# untitled.net
KiCad netlist of a schematic drawn in EAGLE
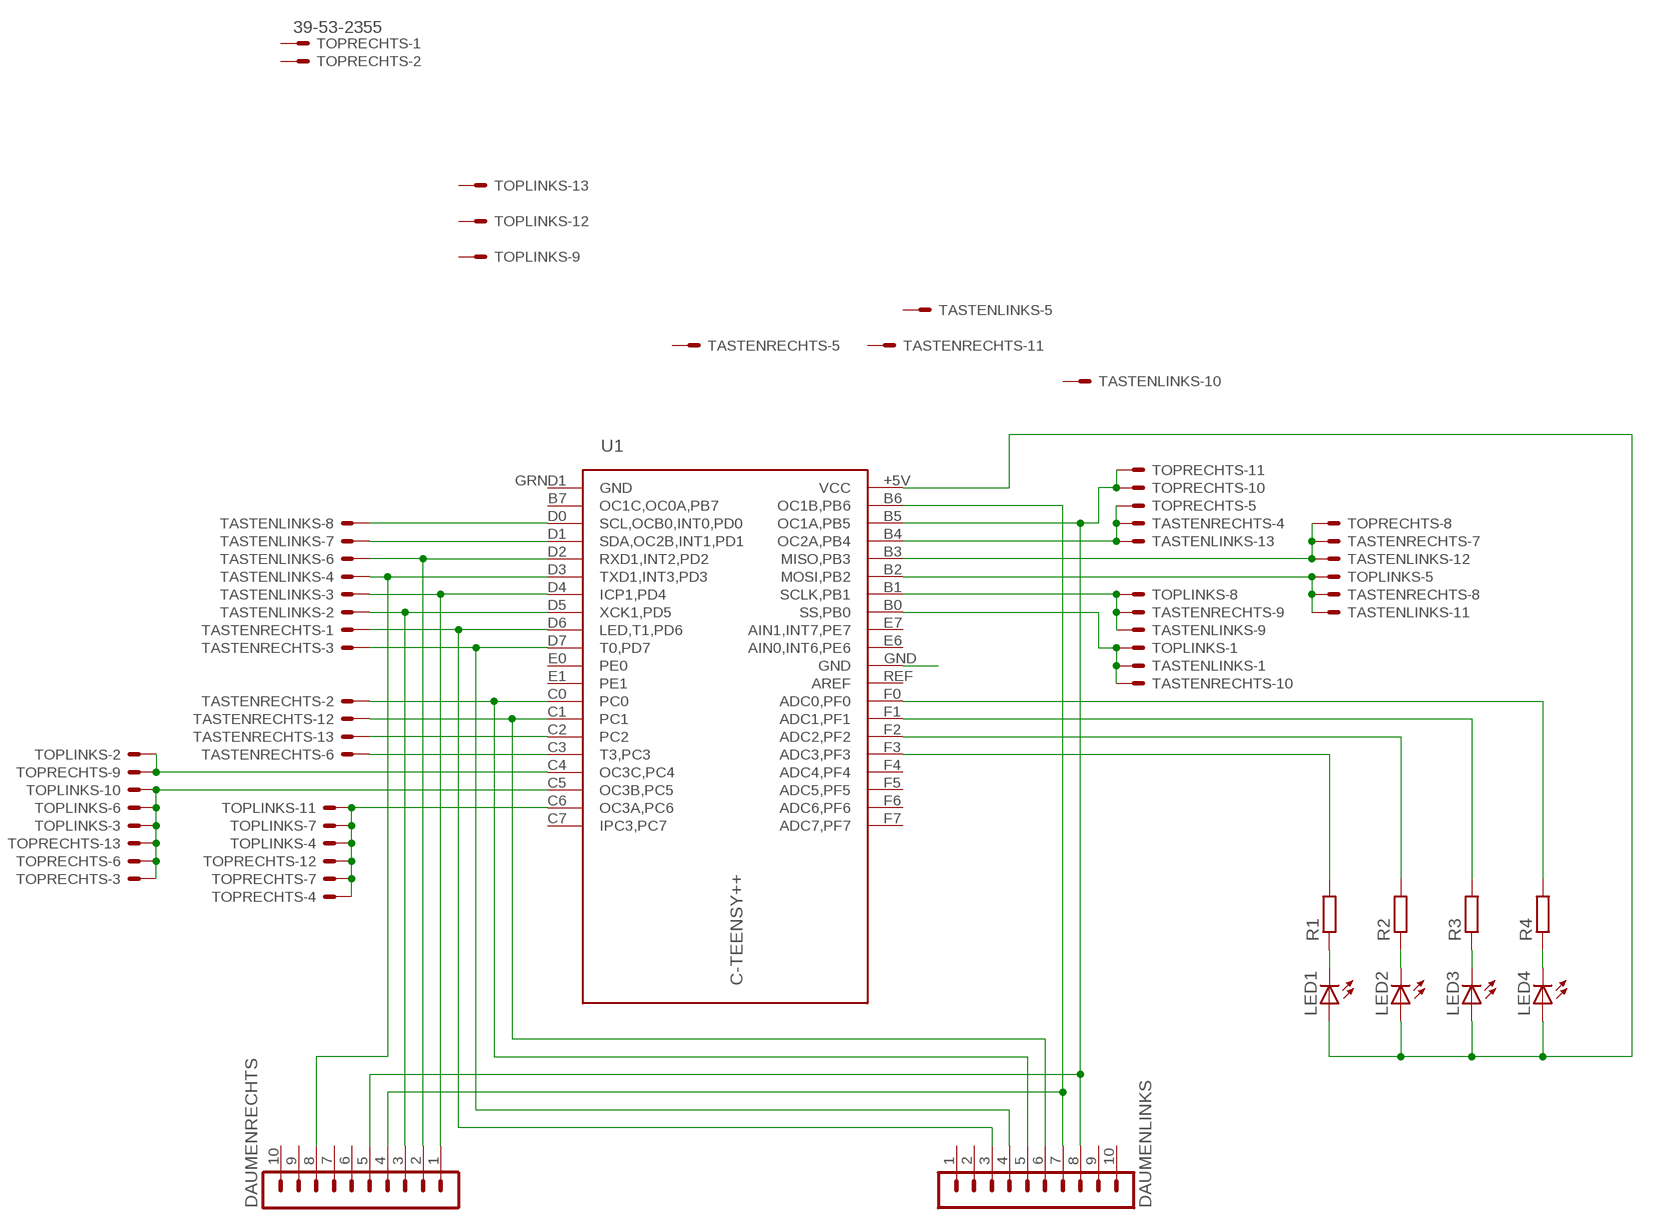
[diagram p0: schematic, sheet 1]

(export (version "E")
  (design (tool "Eeschema 10.0.6"))
  (components
    (comp (ref "DAUMENLINKS")
      (value "MA10-1")
      (footprint "eagle-import:MA10-1")
      (libsource (lib "eagle-import") (part "MA10-1"))
    )
    (comp (ref "DAUMENRECHTS")
      (value "MA10-1")
      (footprint "eagle-import:MA10-1")
      (libsource (lib "eagle-import") (part "MA10-1"))
    )
    (comp (ref "LED1")
      (value "LED3MM")
      (footprint "eagle-import:LED3MM")
      (libsource (lib "eagle-import") (part "LED3MM"))
    )
    (comp (ref "LED2")
      (value "LED3MM")
      (footprint "eagle-import:LED3MM")
      (libsource (lib "eagle-import") (part "LED3MM"))
    )
    (comp (ref "LED3")
      (value "LED3MM")
      (footprint "eagle-import:LED3MM")
      (libsource (lib "eagle-import") (part "LED3MM"))
    )
    (comp (ref "LED4")
      (value "LED3MM")
      (footprint "eagle-import:LED3MM")
      (libsource (lib "eagle-import") (part "LED3MM"))
    )
    (comp (ref "R1")
      (value "R-EU_R1206")
      (footprint "eagle-import:R1206")
      (libsource (lib "eagle-import") (part "R-EU_R1206"))
    )
    (comp (ref "R2")
      (value "R-EU_R1206")
      (footprint "eagle-import:R1206")
      (libsource (lib "eagle-import") (part "R-EU_R1206"))
    )
    (comp (ref "R3")
      (value "R-EU_R1206")
      (footprint "eagle-import:R1206")
      (libsource (lib "eagle-import") (part "R-EU_R1206"))
    )
    (comp (ref "R4")
      (value "R-EU_R1206")
      (footprint "eagle-import:R1206")
      (libsource (lib "eagle-import") (part "R-EU_R1206"))
    )
    (comp (ref "TASTENLINKS")
      (value "39-53-2355")
      (footprint "eagle-import:39-53-2135")
      (libsource (lib "eagle-import") (part "39-53-2355"))
    )
    (comp (ref "TASTENRECHTS")
      (value "39-53-2355")
      (footprint "eagle-import:39-53-2135")
      (libsource (lib "eagle-import") (part "39-53-2355"))
    )
    (comp (ref "TOPLINKS")
      (value "39-53-2355")
      (footprint "eagle-import:39-53-2135")
      (libsource (lib "eagle-import") (part "39-53-2355"))
    )
    (comp (ref "TOPRECHTS")
      (value "39-53-2355")
      (footprint "eagle-import:39-53-2135")
      (libsource (lib "eagle-import") (part "39-53-2355"))
    )
    (comp (ref "U1")
      (value "C-TEENSY++")
      (footprint "eagle-import:TEENSY++")
      (libsource (lib "eagle-import") (part "C-TEENSY++"))
    )
  )
  (nets
    (net (code "1") (name "/GND") (class "Default")
      (node (ref "U1") (pin "GRND1") (pinfunction "GND_GRND1") (pintype "power_in"))
    )
    (net (code "2") (name "Net-(LED1-C)") (class "Default")
      (node (ref "LED1") (pin "K") (pinfunction "C_K") (pintype "passive"))
      (node (ref "R1") (pin "1") (pinfunction "1_1") (pintype "passive"))
    )
    (net (code "3") (name "Net-(LED2-C)") (class "Default")
      (node (ref "LED2") (pin "K") (pinfunction "C_K") (pintype "passive"))
      (node (ref "R2") (pin "1") (pinfunction "1_1") (pintype "passive"))
    )
    (net (code "4") (name "Net-(LED3-C)") (class "Default")
      (node (ref "LED3") (pin "K") (pinfunction "C_K") (pintype "passive"))
      (node (ref "R3") (pin "1") (pinfunction "1_1") (pintype "passive"))
    )
    (net (code "5") (name "Net-(LED4-C)") (class "Default")
      (node (ref "LED4") (pin "K") (pinfunction "C_K") (pintype "passive"))
      (node (ref "R4") (pin "1") (pinfunction "1_1") (pintype "passive"))
    )
    (net (code "6") (name "Net-(TASTENLINKSA-S)") (class "Default")
      (node (ref "TASTENLINKS") (pin "P$1") (pinfunction "S_P$1") (pintype "passive"))
      (node (ref "TASTENRECHTS") (pin "P$10") (pinfunction "S_P$10") (pintype "passive"))
      (node (ref "TOPLINKS") (pin "P$1") (pinfunction "S_P$1") (pintype "passive"))
      (node (ref "U1") (pin "B0") (pinfunction "SS,PB0_B0") (pintype "bidirectional"))
    )
    (net (code "7") (name "Net-(TASTENLINKSC-S)") (class "Default")
      (node (ref "TASTENLINKS") (pin "P$11") (pinfunction "S_P$11") (pintype "passive"))
      (node (ref "TASTENRECHTS") (pin "P$8") (pinfunction "S_P$8") (pintype "passive"))
      (node (ref "TOPLINKS") (pin "P$5") (pinfunction "S_P$5") (pintype "passive"))
      (node (ref "U1") (pin "B2") (pinfunction "MOSI,PB2_B2") (pintype "bidirectional"))
    )
    (net (code "8") (name "Net-(TASTENLINKSD-S)") (class "Default")
      (node (ref "TASTENLINKS") (pin "P$12") (pinfunction "S_P$12") (pintype "passive"))
      (node (ref "TASTENRECHTS") (pin "P$7") (pinfunction "S_P$7") (pintype "passive"))
      (node (ref "TOPRECHTS") (pin "P$8") (pinfunction "S_P$8") (pintype "passive"))
      (node (ref "U1") (pin "B3") (pinfunction "MISO,PB3_B3") (pintype "bidirectional"))
    )
    (net (code "9") (name "Net-(TASTENLINKSE-S)") (class "Default")
      (node (ref "TASTENLINKS") (pin "P$13") (pinfunction "S_P$13") (pintype "passive"))
      (node (ref "TASTENRECHTS") (pin "P$4") (pinfunction "S_P$4") (pintype "passive"))
      (node (ref "TOPRECHTS") (pin "P$5") (pinfunction "S_P$5") (pintype "passive"))
      (node (ref "U1") (pin "B4") (pinfunction "OC2A,PB4_B4") (pintype "bidirectional"))
    )
    (net (code "10") (name "Net-(TASTENLINKSF-S)") (class "Default")
      (node (ref "DAUMENRECHTS") (pin "3") (pinfunction "3_3") (pintype "passive"))
      (node (ref "TASTENLINKS") (pin "P$2") (pinfunction "S_P$2") (pintype "passive"))
      (node (ref "U1") (pin "D5") (pinfunction "XCK1,PD5_D5") (pintype "bidirectional"))
    )
    (net (code "11") (name "Net-(TASTENLINKSG-S)") (class "Default")
      (node (ref "DAUMENRECHTS") (pin "1") (pinfunction "1_1") (pintype "passive"))
      (node (ref "TASTENLINKS") (pin "P$3") (pinfunction "S_P$3") (pintype "passive"))
      (node (ref "U1") (pin "D4") (pinfunction "ICP1,PD4_D4") (pintype "bidirectional"))
    )
    (net (code "12") (name "Net-(TASTENLINKSH-S)") (class "Default")
      (node (ref "DAUMENRECHTS") (pin "8") (pinfunction "8_8") (pintype "passive"))
      (node (ref "TASTENLINKS") (pin "P$4") (pinfunction "S_P$4") (pintype "passive"))
      (node (ref "U1") (pin "D3") (pinfunction "TXD1,INT3,PD3_D3") (pintype "bidirectional"))
    )
    (net (code "13") (name "Net-(TASTENLINKSJ-S)") (class "Default")
      (node (ref "DAUMENRECHTS") (pin "2") (pinfunction "2_2") (pintype "passive"))
      (node (ref "TASTENLINKS") (pin "P$6") (pinfunction "S_P$6") (pintype "passive"))
      (node (ref "U1") (pin "D2") (pinfunction "RXD1,INT2,PD2_D2") (pintype "bidirectional"))
    )
    (net (code "14") (name "Net-(TASTENLINKSK-S)") (class "Default")
      (node (ref "TASTENLINKS") (pin "P$7") (pinfunction "S_P$7") (pintype "passive"))
      (node (ref "U1") (pin "D1") (pinfunction "SDA,OC2B,INT1,PD1_D1") (pintype "bidirectional"))
    )
    (net (code "15") (name "Net-(TASTENLINKSL-S)") (class "Default")
      (node (ref "TASTENLINKS") (pin "P$8") (pinfunction "S_P$8") (pintype "passive"))
      (node (ref "U1") (pin "D0") (pinfunction "SCL,OCB0,INT0,PD0_D0") (pintype "bidirectional"))
    )
    (net (code "16") (name "Net-(TASTENLINKSM-S)") (class "Default")
      (node (ref "TASTENLINKS") (pin "P$9") (pinfunction "S_P$9") (pintype "passive"))
      (node (ref "TASTENRECHTS") (pin "P$9") (pinfunction "S_P$9") (pintype "passive"))
      (node (ref "TOPLINKS") (pin "P$8") (pinfunction "S_P$8") (pintype "passive"))
      (node (ref "U1") (pin "B1") (pinfunction "SCLK,PB1_B1") (pintype "bidirectional"))
    )
    (net (code "17") (name "Net-(TASTENRECHTSA-S)") (class "Default")
      (node (ref "DAUMENLINKS") (pin "3") (pinfunction "3_3") (pintype "passive"))
      (node (ref "TASTENRECHTS") (pin "P$1") (pinfunction "S_P$1") (pintype "passive"))
      (node (ref "U1") (pin "D6") (pinfunction "LED,T1,PD6_D6") (pintype "bidirectional"))
    )
    (net (code "18") (name "Net-(TASTENRECHTSD-S)") (class "Default")
      (node (ref "DAUMENLINKS") (pin "6") (pinfunction "6_6") (pintype "passive"))
      (node (ref "TASTENRECHTS") (pin "P$12") (pinfunction "S_P$12") (pintype "passive"))
      (node (ref "U1") (pin "C1") (pinfunction "PC1_C1") (pintype "bidirectional"))
    )
    (net (code "19") (name "Net-(TASTENRECHTSE-S)") (class "Default")
      (node (ref "TASTENRECHTS") (pin "P$13") (pinfunction "S_P$13") (pintype "passive"))
      (node (ref "U1") (pin "C2") (pinfunction "PC2_C2") (pintype "bidirectional"))
    )
    (net (code "20") (name "Net-(TASTENRECHTSF-S)") (class "Default")
      (node (ref "DAUMENLINKS") (pin "5") (pinfunction "5_5") (pintype "passive"))
      (node (ref "TASTENRECHTS") (pin "P$2") (pinfunction "S_P$2") (pintype "passive"))
      (node (ref "U1") (pin "C0") (pinfunction "PC0_C0") (pintype "bidirectional"))
    )
    (net (code "21") (name "Net-(TASTENRECHTSG-S)") (class "Default")
      (node (ref "DAUMENLINKS") (pin "4") (pinfunction "4_4") (pintype "passive"))
      (node (ref "TASTENRECHTS") (pin "P$3") (pinfunction "S_P$3") (pintype "passive"))
      (node (ref "U1") (pin "D7") (pinfunction "T0,PD7_D7") (pintype "bidirectional"))
    )
    (net (code "22") (name "Net-(TASTENRECHTSJ-S)") (class "Default")
      (node (ref "TASTENRECHTS") (pin "P$6") (pinfunction "S_P$6") (pintype "passive"))
      (node (ref "U1") (pin "C3") (pinfunction "T3,PC3_C3") (pintype "bidirectional"))
    )
    (net (code "23") (name "Net-(TOPLINKSB-S)") (class "Default")
      (node (ref "TOPLINKS") (pin "P$10") (pinfunction "S_P$10") (pintype "passive"))
      (node (ref "TOPLINKS") (pin "P$3") (pinfunction "S_P$3") (pintype "passive"))
      (node (ref "TOPLINKS") (pin "P$6") (pinfunction "S_P$6") (pintype "passive"))
      (node (ref "TOPRECHTS") (pin "P$13") (pinfunction "S_P$13") (pintype "passive"))
      (node (ref "TOPRECHTS") (pin "P$3") (pinfunction "S_P$3") (pintype "passive"))
      (node (ref "TOPRECHTS") (pin "P$6") (pinfunction "S_P$6") (pintype "passive"))
      (node (ref "U1") (pin "C5") (pinfunction "OC3B,PC5_C5") (pintype "bidirectional"))
    )
    (net (code "24") (name "Net-(TOPLINKSC-S)") (class "Default")
      (node (ref "TOPLINKS") (pin "P$11") (pinfunction "S_P$11") (pintype "passive"))
      (node (ref "TOPLINKS") (pin "P$4") (pinfunction "S_P$4") (pintype "passive"))
      (node (ref "TOPLINKS") (pin "P$7") (pinfunction "S_P$7") (pintype "passive"))
      (node (ref "TOPRECHTS") (pin "P$12") (pinfunction "S_P$12") (pintype "passive"))
      (node (ref "TOPRECHTS") (pin "P$4") (pinfunction "S_P$4") (pintype "passive"))
      (node (ref "TOPRECHTS") (pin "P$7") (pinfunction "S_P$7") (pintype "passive"))
      (node (ref "U1") (pin "C6") (pinfunction "OC3A,PC6_C6") (pintype "bidirectional"))
    )
    (net (code "25") (name "Net-(TOPLINKSF-S)") (class "Default")
      (node (ref "TOPLINKS") (pin "P$2") (pinfunction "S_P$2") (pintype "passive"))
      (node (ref "TOPRECHTS") (pin "P$9") (pinfunction "S_P$9") (pintype "passive"))
      (node (ref "U1") (pin "C4") (pinfunction "OC3C,PC4_C4") (pintype "bidirectional"))
    )
    (net (code "26") (name "Net-(TOPRECHTSB-S)") (class "Default")
      (node (ref "DAUMENLINKS") (pin "8") (pinfunction "8_8") (pintype "passive"))
      (node (ref "DAUMENRECHTS") (pin "5") (pinfunction "5_5") (pintype "passive"))
      (node (ref "TOPRECHTS") (pin "P$10") (pinfunction "S_P$10") (pintype "passive"))
      (node (ref "TOPRECHTS") (pin "P$11") (pinfunction "S_P$11") (pintype "passive"))
      (node (ref "U1") (pin "B5") (pinfunction "OC1A,PB5_B5") (pintype "bidirectional"))
    )
    (net (code "27") (name "Net-(U1-ADC0,PF0)") (class "Default")
      (node (ref "R4") (pin "2") (pinfunction "2_2") (pintype "passive"))
      (node (ref "U1") (pin "F0") (pinfunction "ADC0,PF0_F0") (pintype "bidirectional"))
    )
    (net (code "28") (name "Net-(U1-ADC1,PF1)") (class "Default")
      (node (ref "R3") (pin "2") (pinfunction "2_2") (pintype "passive"))
      (node (ref "U1") (pin "F1") (pinfunction "ADC1,PF1_F1") (pintype "bidirectional"))
    )
    (net (code "29") (name "Net-(U1-ADC2,PF2)") (class "Default")
      (node (ref "R2") (pin "2") (pinfunction "2_2") (pintype "passive"))
      (node (ref "U1") (pin "F2") (pinfunction "ADC2,PF2_F2") (pintype "bidirectional"))
    )
    (net (code "30") (name "Net-(U1-ADC3,PF3)") (class "Default")
      (node (ref "R1") (pin "2") (pinfunction "2_2") (pintype "passive"))
      (node (ref "U1") (pin "F3") (pinfunction "ADC3,PF3_F3") (pintype "bidirectional"))
    )
    (net (code "31") (name "Net-(U1-OC1B,PB6)") (class "Default")
      (node (ref "DAUMENLINKS") (pin "7") (pinfunction "7_7") (pintype "passive"))
      (node (ref "DAUMENRECHTS") (pin "4") (pinfunction "4_4") (pintype "passive"))
      (node (ref "U1") (pin "B6") (pinfunction "OC1B,PB6_B6") (pintype "bidirectional"))
    )
    (net (code "32") (name "Net-(U1-VCC)") (class "Default")
      (node (ref "LED1") (pin "A") (pinfunction "A_A") (pintype "passive"))
      (node (ref "LED2") (pin "A") (pinfunction "A_A") (pintype "passive"))
      (node (ref "LED3") (pin "A") (pinfunction "A_A") (pintype "passive"))
      (node (ref "LED4") (pin "A") (pinfunction "A_A") (pintype "passive"))
      (node (ref "U1") (pin "+5V") (pinfunction "VCC_+5V") (pintype "power_in"))
    )
    (net (code "33") (name "unconnected-(DAUMENLINKS-Pad1)") (class "Default")
      (node (ref "DAUMENLINKS") (pin "1") (pinfunction "1_1") (pintype "passive"))
    )
    (net (code "34") (name "unconnected-(DAUMENLINKS-Pad2)") (class "Default")
      (node (ref "DAUMENLINKS") (pin "2") (pinfunction "2_2") (pintype "passive"))
    )
    (net (code "35") (name "unconnected-(DAUMENLINKS-Pad9)") (class "Default")
      (node (ref "DAUMENLINKS") (pin "9") (pinfunction "9_9") (pintype "passive"))
    )
    (net (code "36") (name "unconnected-(DAUMENLINKS-Pad10)") (class "Default")
      (node (ref "DAUMENLINKS") (pin "10") (pinfunction "10_10") (pintype "passive"))
    )
    (net (code "37") (name "unconnected-(DAUMENRECHTS-Pad6)") (class "Default")
      (node (ref "DAUMENRECHTS") (pin "6") (pinfunction "6_6") (pintype "passive"))
    )
    (net (code "38") (name "unconnected-(DAUMENRECHTS-Pad7)") (class "Default")
      (node (ref "DAUMENRECHTS") (pin "7") (pinfunction "7_7") (pintype "passive"))
    )
    (net (code "39") (name "unconnected-(DAUMENRECHTS-Pad9)") (class "Default")
      (node (ref "DAUMENRECHTS") (pin "9") (pinfunction "9_9") (pintype "passive"))
    )
    (net (code "40") (name "unconnected-(DAUMENRECHTS-Pad10)") (class "Default")
      (node (ref "DAUMENRECHTS") (pin "10") (pinfunction "10_10") (pintype "passive"))
    )
    (net (code "41") (name "unconnected-(TASTENLINKSB-S-PadP$10)") (class "Default")
      (node (ref "TASTENLINKS") (pin "P$10") (pinfunction "S_P$10") (pintype "passive"))
    )
    (net (code "42") (name "unconnected-(TASTENLINKSI-S-PadP$5)") (class "Default")
      (node (ref "TASTENLINKS") (pin "P$5") (pinfunction "S_P$5") (pintype "passive"))
    )
    (net (code "43") (name "unconnected-(TASTENRECHTSC-S-PadP$11)") (class "Default")
      (node (ref "TASTENRECHTS") (pin "P$11") (pinfunction "S_P$11") (pintype "passive"))
    )
    (net (code "44") (name "unconnected-(TASTENRECHTSI-S-PadP$5)") (class "Default")
      (node (ref "TASTENRECHTS") (pin "P$5") (pinfunction "S_P$5") (pintype "passive"))
    )
    (net (code "45") (name "unconnected-(TOPLINKSD-S-PadP$12)") (class "Default")
      (node (ref "TOPLINKS") (pin "P$12") (pinfunction "S_P$12") (pintype "passive"))
    )
    (net (code "46") (name "unconnected-(TOPLINKSE-S-PadP$13)") (class "Default")
      (node (ref "TOPLINKS") (pin "P$13") (pinfunction "S_P$13") (pintype "passive"))
    )
    (net (code "47") (name "unconnected-(TOPLINKSM-S-PadP$9)") (class "Default")
      (node (ref "TOPLINKS") (pin "P$9") (pinfunction "S_P$9") (pintype "passive"))
    )
    (net (code "48") (name "unconnected-(TOPRECHTSA-S-PadP$1)") (class "Default")
      (node (ref "TOPRECHTS") (pin "P$1") (pinfunction "S_P$1") (pintype "passive"))
    )
    (net (code "49") (name "unconnected-(TOPRECHTSF-S-PadP$2)") (class "Default")
      (node (ref "TOPRECHTS") (pin "P$2") (pinfunction "S_P$2") (pintype "passive"))
    )
    (net (code "50") (name "unconnected-(U1-ADC4,PF4-PadF4)") (class "Default")
      (node (ref "U1") (pin "F4") (pinfunction "ADC4,PF4_F4") (pintype "bidirectional"))
    )
    (net (code "51") (name "unconnected-(U1-ADC5,PF5-PadF5)") (class "Default")
      (node (ref "U1") (pin "F5") (pinfunction "ADC5,PF5_F5") (pintype "bidirectional"))
    )
    (net (code "52") (name "unconnected-(U1-ADC6,PF6-PadF6)") (class "Default")
      (node (ref "U1") (pin "F6") (pinfunction "ADC6,PF6_F6") (pintype "bidirectional"))
    )
    (net (code "53") (name "unconnected-(U1-ADC7,PF7-PadF7)") (class "Default")
      (node (ref "U1") (pin "F7") (pinfunction "ADC7,PF7_F7") (pintype "bidirectional"))
    )
    (net (code "54") (name "unconnected-(U1-AIN0,INT6,PE6-PadE6)") (class "Default")
      (node (ref "U1") (pin "E6") (pinfunction "AIN0,INT6,PE6_E6") (pintype "bidirectional"))
    )
    (net (code "55") (name "unconnected-(U1-AIN1,INT7,PE7-PadE7)") (class "Default")
      (node (ref "U1") (pin "E7") (pinfunction "AIN1,INT7,PE7_E7") (pintype "bidirectional"))
    )
    (net (code "56") (name "unconnected-(U1-AREF-PadREF)") (class "Default")
      (node (ref "U1") (pin "REF") (pinfunction "AREF_REF") (pintype "input"))
    )
    (net (code "57") (name "unconnected-(U1-IPC3,PC7-PadC7)") (class "Default")
      (node (ref "U1") (pin "C7") (pinfunction "IPC3,PC7_C7") (pintype "bidirectional"))
    )
    (net (code "58") (name "unconnected-(U1-OC1C,OC0A,PB7-PadB7)") (class "Default")
      (node (ref "U1") (pin "B7") (pinfunction "OC1C,OC0A,PB7_B7") (pintype "bidirectional"))
    )
    (net (code "59") (name "unconnected-(U1-PE0-PadE0)") (class "Default")
      (node (ref "U1") (pin "E0") (pinfunction "PE0_E0") (pintype "bidirectional"))
    )
    (net (code "60") (name "unconnected-(U1-PE1-PadE1)") (class "Default")
      (node (ref "U1") (pin "E1") (pinfunction "PE1_E1") (pintype "bidirectional"))
    )
    (net (code "61") (name "unconnected-(U1-PadGND)") (class "Default")
      (node (ref "U1") (pin "GND") (pinfunction "GND_GND") (pintype "power_in"))
    )
  )
)
